# V2.net
KiCad netlist of a schematic drawn in EAGLE
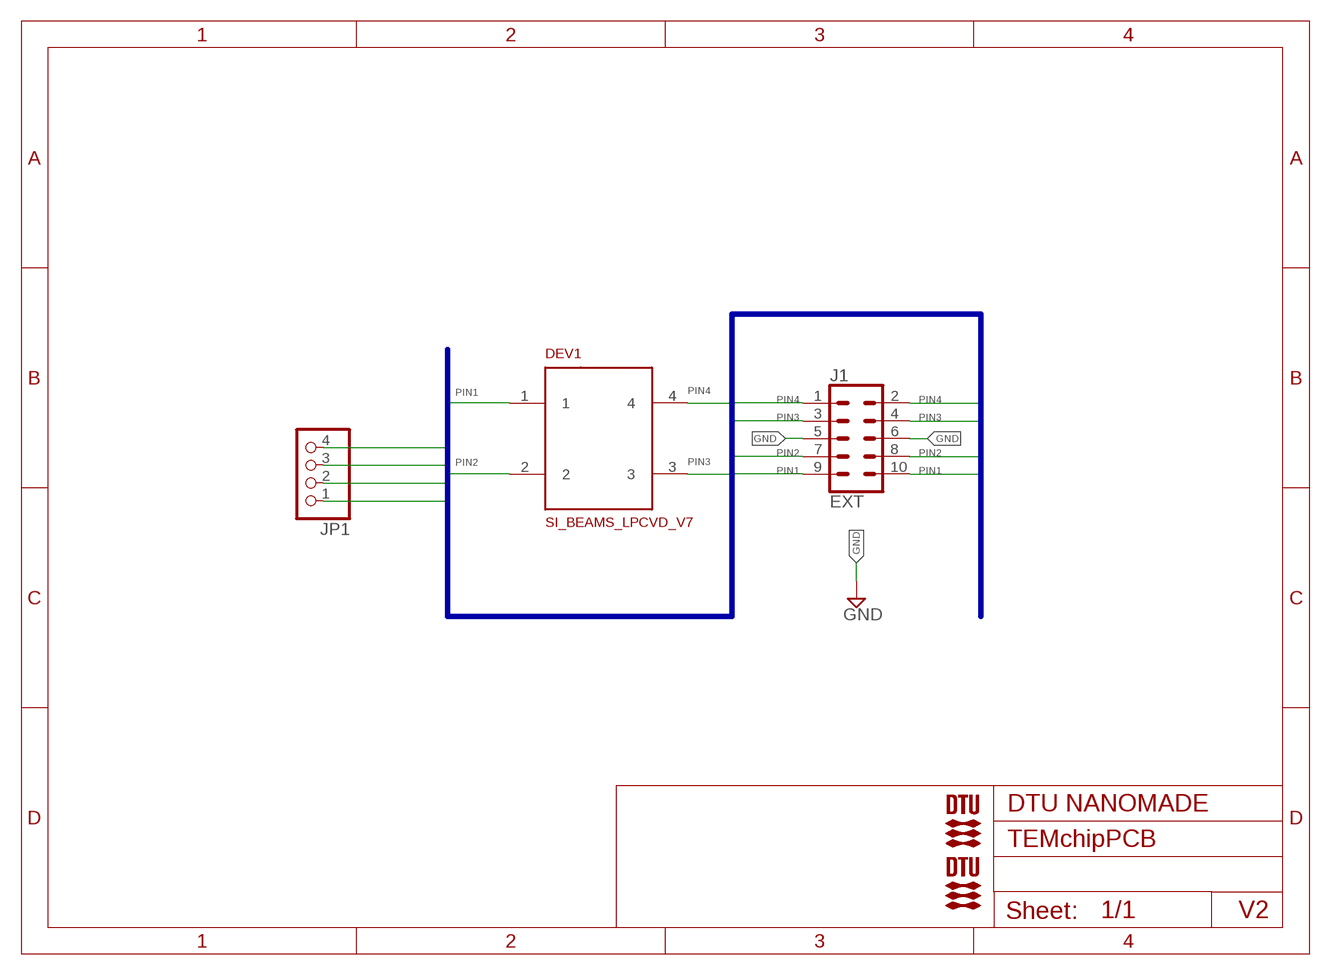
[diagram p0: schematic, sheet 1]

(export (version "E")
  (design (tool "Eeschema 10.0.6"))
  (components
    (comp (ref "DEV1")
      (value "SI_BEAMS_LPCVD_V7")
      (footprint "eagle-import:SI_BEAMS_LPCVD_V7")
      (libsource (lib "eagle-import") (part "SI_BEAMS_LPCVD_V7"))
    )
    (comp (ref "J1")
      (value "EXT")
      (footprint "eagle-import:2X5-SHROUDED")
      (libsource (lib "eagle-import") (part "CONN_05X2SHD"))
    )
    (comp (ref "JP1")
      (value "PINHD-1X4")
      (footprint "eagle-import:1X04")
      (libsource (lib "eagle-import") (part "PINHD-1X4"))
    )
    (comp (ref "U$1")
      (value "DTU_LOGO")
      (footprint "eagle-import:DTU")
      (libsource (lib "eagle-import") (part "DTU_LOGO"))
    )
    (comp (ref "U$2")
      (value "DTU_LOGO")
      (footprint "eagle-import:DTU")
      (libsource (lib "eagle-import") (part "DTU_LOGO"))
    )
  )
  (nets
    (net (code "1") (name "/PIN1") (class "Default")
      (node (ref "DEV1") (pin "1") (pinfunction "1_1") (pintype "bidirectional"))
      (node (ref "J1") (pin "10") (pinfunction "10_10") (pintype "passive"))
      (node (ref "J1") (pin "9") (pinfunction "9_9") (pintype "passive"))
      (node (ref "JP1") (pin "1") (pinfunction "1_1") (pintype "passive"))
    )
    (net (code "2") (name "/PIN2") (class "Default")
      (node (ref "DEV1") (pin "2") (pinfunction "2_2") (pintype "bidirectional"))
      (node (ref "J1") (pin "7") (pinfunction "7_7") (pintype "passive"))
      (node (ref "J1") (pin "8") (pinfunction "8_8") (pintype "passive"))
      (node (ref "JP1") (pin "2") (pinfunction "2_2") (pintype "passive"))
    )
    (net (code "3") (name "/PIN3") (class "Default")
      (node (ref "DEV1") (pin "3") (pinfunction "3_3") (pintype "bidirectional"))
      (node (ref "J1") (pin "3") (pinfunction "3_3") (pintype "passive"))
      (node (ref "J1") (pin "4") (pinfunction "4_4") (pintype "passive"))
      (node (ref "JP1") (pin "3") (pinfunction "3_3") (pintype "passive"))
    )
    (net (code "4") (name "/PIN4") (class "Default")
      (node (ref "DEV1") (pin "4") (pinfunction "4_4") (pintype "bidirectional"))
      (node (ref "J1") (pin "1") (pinfunction "1_1") (pintype "passive"))
      (node (ref "J1") (pin "2") (pinfunction "2_2") (pintype "passive"))
      (node (ref "JP1") (pin "4") (pinfunction "4_4") (pintype "passive"))
    )
    (net (code "5") (name "GND") (class "Default")
      (node (ref "J1") (pin "5") (pinfunction "5_5") (pintype "passive"))
      (node (ref "J1") (pin "6") (pinfunction "6_6") (pintype "passive"))
    )
  )
)
